# osc.net
KiCad netlist of a schematic drawn in EAGLE
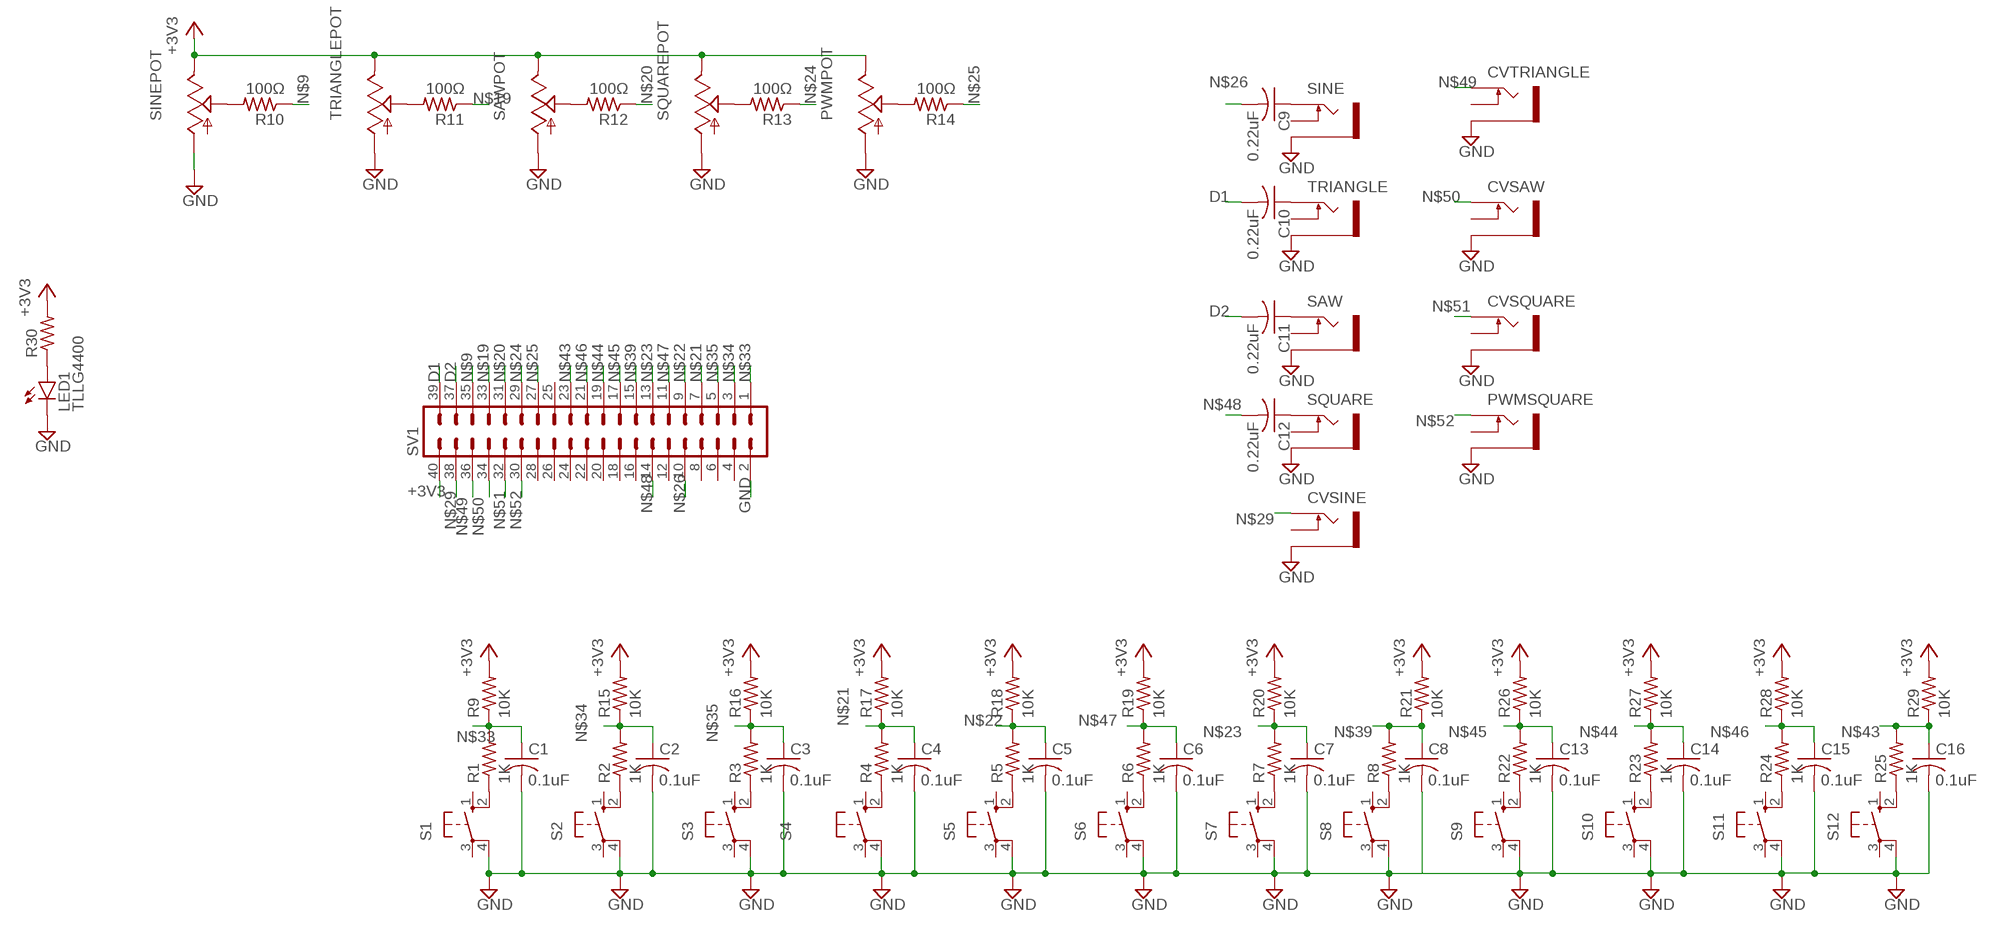
[diagram p0: schematic, sheet 1]

(export (version "E")
  (design (tool "Eeschema 10.0.6"))
  (components
    (comp (ref "C1")
      (value "0.1uF")
      (footprint "eagle-import:C025-024X044")
      (libsource (lib "eagle-import") (part "C-US025-024X044"))
    )
    (comp (ref "C2")
      (value "0.1uF")
      (footprint "eagle-import:C025-024X044")
      (libsource (lib "eagle-import") (part "C-US025-024X044"))
    )
    (comp (ref "C3")
      (value "0.1uF")
      (footprint "eagle-import:C025-024X044")
      (libsource (lib "eagle-import") (part "C-US025-024X044"))
    )
    (comp (ref "C4")
      (value "0.1uF")
      (footprint "eagle-import:C025-024X044")
      (libsource (lib "eagle-import") (part "C-US025-024X044"))
    )
    (comp (ref "C5")
      (value "0.1uF")
      (footprint "eagle-import:C025-024X044")
      (libsource (lib "eagle-import") (part "C-US025-024X044"))
    )
    (comp (ref "C6")
      (value "0.1uF")
      (footprint "eagle-import:C025-024X044")
      (libsource (lib "eagle-import") (part "C-US025-024X044"))
    )
    (comp (ref "C7")
      (value "0.1uF")
      (footprint "eagle-import:C025-024X044")
      (libsource (lib "eagle-import") (part "C-US025-024X044"))
    )
    (comp (ref "C8")
      (value "0.1uF")
      (footprint "eagle-import:C025-024X044")
      (libsource (lib "eagle-import") (part "C-US025-024X044"))
    )
    (comp (ref "C9")
      (value "0.22uF")
      (footprint "eagle-import:C025-024X044")
      (libsource (lib "eagle-import") (part "C-US025-024X044"))
    )
    (comp (ref "C10")
      (value "0.22uF")
      (footprint "eagle-import:C025-024X044")
      (libsource (lib "eagle-import") (part "C-US025-024X044"))
    )
    (comp (ref "C11")
      (value "0.22uF")
      (footprint "eagle-import:C025-024X044")
      (libsource (lib "eagle-import") (part "C-US025-024X044"))
    )
    (comp (ref "C12")
      (value "0.22uF")
      (footprint "eagle-import:C025-024X044")
      (libsource (lib "eagle-import") (part "C-US025-024X044"))
    )
    (comp (ref "C13")
      (value "0.1uF")
      (footprint "eagle-import:C025-024X044")
      (libsource (lib "eagle-import") (part "C-US025-024X044"))
    )
    (comp (ref "C14")
      (value "0.1uF")
      (footprint "eagle-import:C025-024X044")
      (libsource (lib "eagle-import") (part "C-US025-024X044"))
    )
    (comp (ref "C15")
      (value "0.1uF")
      (footprint "eagle-import:C025-024X044")
      (libsource (lib "eagle-import") (part "C-US025-024X044"))
    )
    (comp (ref "C16")
      (value "0.1uF")
      (footprint "eagle-import:C025-024X044")
      (libsource (lib "eagle-import") (part "C-US025-024X044"))
    )
    (comp (ref "CVSAW")
      (value "THONKICONNNEW")
      (footprint "eagle-import:WQP-PJ301M-12_JACK")
      (libsource (lib "eagle-import") (part "THONKICONNNEW"))
    )
    (comp (ref "CVSINE")
      (value "THONKICONNNEW")
      (footprint "eagle-import:WQP-PJ301M-12_JACK")
      (libsource (lib "eagle-import") (part "THONKICONNNEW"))
    )
    (comp (ref "CVSQUARE")
      (value "THONKICONNNEW")
      (footprint "eagle-import:WQP-PJ301M-12_JACK")
      (libsource (lib "eagle-import") (part "THONKICONNNEW"))
    )
    (comp (ref "CVTRIANGLE")
      (value "THONKICONNNEW")
      (footprint "eagle-import:WQP-PJ301M-12_JACK")
      (libsource (lib "eagle-import") (part "THONKICONNNEW"))
    )
    (comp (ref "LED1")
      (value "TLLG4400")
      (footprint "eagle-import:LED3MM")
      (fields (field (name "MF") "VISHAY SEMICONDUCTOR"))
      (libsource (lib "eagle-import") (part "TLLG4400"))
    )
    (comp (ref "PWMPOT")
      (value "9MM_SNAP-IN_POT_")
      (footprint "eagle-import:9MM_SNAP-IN_POT")
      (libsource (lib "eagle-import") (part "9MM_SNAP-IN_POT_"))
    )
    (comp (ref "PWMSQUARE")
      (value "THONKICONNNEW")
      (footprint "eagle-import:WQP-PJ301M-12_JACK")
      (libsource (lib "eagle-import") (part "THONKICONNNEW"))
    )
    (comp (ref "R1")
      (value "1K")
      (footprint "eagle-import:0207_10")
      (libsource (lib "eagle-import") (part "R-US_0207/10"))
    )
    (comp (ref "R2")
      (value "1K")
      (footprint "eagle-import:0207_10")
      (libsource (lib "eagle-import") (part "R-US_0207/10"))
    )
    (comp (ref "R3")
      (value "1K")
      (footprint "eagle-import:0207_10")
      (libsource (lib "eagle-import") (part "R-US_0207/10"))
    )
    (comp (ref "R4")
      (value "1K")
      (footprint "eagle-import:0207_10")
      (libsource (lib "eagle-import") (part "R-US_0207/10"))
    )
    (comp (ref "R5")
      (value "1K")
      (footprint "eagle-import:0207_10")
      (libsource (lib "eagle-import") (part "R-US_0207/10"))
    )
    (comp (ref "R6")
      (value "1K")
      (footprint "eagle-import:0207_10")
      (libsource (lib "eagle-import") (part "R-US_0207/10"))
    )
    (comp (ref "R7")
      (value "1K")
      (footprint "eagle-import:0207_10")
      (libsource (lib "eagle-import") (part "R-US_0207/10"))
    )
    (comp (ref "R8")
      (value "1K")
      (footprint "eagle-import:0207_10")
      (libsource (lib "eagle-import") (part "R-US_0207/10"))
    )
    (comp (ref "R9")
      (value "10K")
      (footprint "eagle-import:0207_10")
      (libsource (lib "eagle-import") (part "R-US_0207/10"))
    )
    (comp (ref "R10")
      (value "100Ω")
      (footprint "eagle-import:0207_10")
      (libsource (lib "eagle-import") (part "R-US_0207/10"))
    )
    (comp (ref "R11")
      (value "100Ω")
      (footprint "eagle-import:0207_10")
      (libsource (lib "eagle-import") (part "R-US_0207/10"))
    )
    (comp (ref "R12")
      (value "100Ω")
      (footprint "eagle-import:0207_10")
      (libsource (lib "eagle-import") (part "R-US_0207/10"))
    )
    (comp (ref "R13")
      (value "100Ω")
      (footprint "eagle-import:0207_10")
      (libsource (lib "eagle-import") (part "R-US_0207/10"))
    )
    (comp (ref "R14")
      (value "100Ω")
      (footprint "eagle-import:0207_10")
      (libsource (lib "eagle-import") (part "R-US_0207/10"))
    )
    (comp (ref "R15")
      (value "10K")
      (footprint "eagle-import:0207_10")
      (libsource (lib "eagle-import") (part "R-US_0207/10"))
    )
    (comp (ref "R16")
      (value "10K")
      (footprint "eagle-import:0207_10")
      (libsource (lib "eagle-import") (part "R-US_0207/10"))
    )
    (comp (ref "R17")
      (value "10K")
      (footprint "eagle-import:0207_10")
      (libsource (lib "eagle-import") (part "R-US_0207/10"))
    )
    (comp (ref "R18")
      (value "10K")
      (footprint "eagle-import:0207_10")
      (libsource (lib "eagle-import") (part "R-US_0207/10"))
    )
    (comp (ref "R19")
      (value "10K")
      (footprint "eagle-import:0207_10")
      (libsource (lib "eagle-import") (part "R-US_0207/10"))
    )
    (comp (ref "R20")
      (value "10K")
      (footprint "eagle-import:0207_10")
      (libsource (lib "eagle-import") (part "R-US_0207/10"))
    )
    (comp (ref "R21")
      (value "10K")
      (footprint "eagle-import:0207_10")
      (libsource (lib "eagle-import") (part "R-US_0207/10"))
    )
    (comp (ref "R22")
      (value "1K")
      (footprint "eagle-import:0207_10")
      (libsource (lib "eagle-import") (part "R-US_0207/10"))
    )
    (comp (ref "R23")
      (value "1K")
      (footprint "eagle-import:0207_10")
      (libsource (lib "eagle-import") (part "R-US_0207/10"))
    )
    (comp (ref "R24")
      (value "1K")
      (footprint "eagle-import:0207_10")
      (libsource (lib "eagle-import") (part "R-US_0207/10"))
    )
    (comp (ref "R25")
      (value "1K")
      (footprint "eagle-import:0207_10")
      (libsource (lib "eagle-import") (part "R-US_0207/10"))
    )
    (comp (ref "R26")
      (value "10K")
      (footprint "eagle-import:0207_10")
      (libsource (lib "eagle-import") (part "R-US_0207/10"))
    )
    (comp (ref "R27")
      (value "10K")
      (footprint "eagle-import:0207_10")
      (libsource (lib "eagle-import") (part "R-US_0207/10"))
    )
    (comp (ref "R28")
      (value "10K")
      (footprint "eagle-import:0207_10")
      (libsource (lib "eagle-import") (part "R-US_0207/10"))
    )
    (comp (ref "R29")
      (value "10K")
      (footprint "eagle-import:0207_10")
      (libsource (lib "eagle-import") (part "R-US_0207/10"))
    )
    (comp (ref "R30")
      (value "R-US_0207/10")
      (footprint "eagle-import:0207_10")
      (libsource (lib "eagle-import") (part "R-US_0207/10"))
    )
    (comp (ref "S1")
      (value "10-XX")
      (footprint "eagle-import:B3F-10XX")
      (fields (field (name "MPN") "B3F-1000"))
      (libsource (lib "eagle-import") (part "10-XX"))
    )
    (comp (ref "S2")
      (value "10-XX")
      (footprint "eagle-import:B3F-10XX")
      (fields (field (name "MPN") "B3F-1000"))
      (libsource (lib "eagle-import") (part "10-XX"))
    )
    (comp (ref "S3")
      (value "10-XX")
      (footprint "eagle-import:B3F-10XX")
      (fields (field (name "MPN") "B3F-1000"))
      (libsource (lib "eagle-import") (part "10-XX"))
    )
    (comp (ref "S4")
      (value "10-XX")
      (footprint "eagle-import:B3F-10XX")
      (fields (field (name "MPN") "B3F-1000"))
      (libsource (lib "eagle-import") (part "10-XX"))
    )
    (comp (ref "S5")
      (value "10-XX")
      (footprint "eagle-import:B3F-10XX")
      (fields (field (name "MPN") "B3F-1000"))
      (libsource (lib "eagle-import") (part "10-XX"))
    )
    (comp (ref "S6")
      (value "10-XX")
      (footprint "eagle-import:B3F-10XX")
      (fields (field (name "MPN") "B3F-1000"))
      (libsource (lib "eagle-import") (part "10-XX"))
    )
    (comp (ref "S7")
      (value "10-XX")
      (footprint "eagle-import:B3F-10XX")
      (fields (field (name "MPN") "B3F-1000"))
      (libsource (lib "eagle-import") (part "10-XX"))
    )
    (comp (ref "S8")
      (value "10-XX")
      (footprint "eagle-import:B3F-10XX")
      (fields (field (name "MPN") "B3F-1000"))
      (libsource (lib "eagle-import") (part "10-XX"))
    )
    (comp (ref "S9")
      (value "10-XX")
      (footprint "eagle-import:B3F-10XX")
      (fields (field (name "MPN") "B3F-1000"))
      (libsource (lib "eagle-import") (part "10-XX"))
    )
    (comp (ref "S10")
      (value "10-XX")
      (footprint "eagle-import:B3F-10XX")
      (fields (field (name "MPN") "B3F-1000"))
      (libsource (lib "eagle-import") (part "10-XX"))
    )
    (comp (ref "S11")
      (value "10-XX")
      (footprint "eagle-import:B3F-10XX")
      (fields (field (name "MPN") "B3F-1000"))
      (libsource (lib "eagle-import") (part "10-XX"))
    )
    (comp (ref "S12")
      (value "10-XX")
      (footprint "eagle-import:B3F-10XX")
      (fields (field (name "MPN") "B3F-1000"))
      (libsource (lib "eagle-import") (part "10-XX"))
    )
    (comp (ref "SAW")
      (value "THONKICONNNEW")
      (footprint "eagle-import:WQP-PJ301M-12_JACK")
      (libsource (lib "eagle-import") (part "THONKICONNNEW"))
    )
    (comp (ref "SAWPOT")
      (value "9MM_SNAP-IN_POT_")
      (footprint "eagle-import:9MM_SNAP-IN_POT")
      (libsource (lib "eagle-import") (part "9MM_SNAP-IN_POT_"))
    )
    (comp (ref "SINE")
      (value "THONKICONNNEW")
      (footprint "eagle-import:WQP-PJ301M-12_JACK")
      (libsource (lib "eagle-import") (part "THONKICONNNEW"))
    )
    (comp (ref "SINEPOT")
      (value "9MM_SNAP-IN_POT_")
      (footprint "eagle-import:9MM_SNAP-IN_POT")
      (libsource (lib "eagle-import") (part "9MM_SNAP-IN_POT_"))
    )
    (comp (ref "SQUARE")
      (value "THONKICONNNEW")
      (footprint "eagle-import:WQP-PJ301M-12_JACK")
      (libsource (lib "eagle-import") (part "THONKICONNNEW"))
    )
    (comp (ref "SQUAREPOT")
      (value "9MM_SNAP-IN_POT_")
      (footprint "eagle-import:9MM_SNAP-IN_POT")
      (libsource (lib "eagle-import") (part "9MM_SNAP-IN_POT_"))
    )
    (comp (ref "SV1")
      (value "MA20-2")
      (footprint "eagle-import:MA20-2")
      (libsource (lib "eagle-import") (part "MA20-2"))
    )
    (comp (ref "TRIANGLE")
      (value "THONKICONNNEW")
      (footprint "eagle-import:WQP-PJ301M-12_JACK")
      (libsource (lib "eagle-import") (part "THONKICONNNEW"))
    )
    (comp (ref "TRIANGLEPOT")
      (value "9MM_SNAP-IN_POT_")
      (footprint "eagle-import:9MM_SNAP-IN_POT")
      (libsource (lib "eagle-import") (part "9MM_SNAP-IN_POT_"))
    )
  )
  (nets
    (net (code "1") (name "+3V3") (class "Default")
      (node (ref "PWMPOT") (pin "3") (pinfunction "E_3") (pintype "passive"))
      (node (ref "R15") (pin "2") (pinfunction "2_2") (pintype "passive"))
      (node (ref "R16") (pin "2") (pinfunction "2_2") (pintype "passive"))
      (node (ref "R17") (pin "2") (pinfunction "2_2") (pintype "passive"))
      (node (ref "R18") (pin "2") (pinfunction "2_2") (pintype "passive"))
      (node (ref "R19") (pin "2") (pinfunction "2_2") (pintype "passive"))
      (node (ref "R20") (pin "2") (pinfunction "2_2") (pintype "passive"))
      (node (ref "R21") (pin "2") (pinfunction "2_2") (pintype "passive"))
      (node (ref "R26") (pin "2") (pinfunction "2_2") (pintype "passive"))
      (node (ref "R27") (pin "2") (pinfunction "2_2") (pintype "passive"))
      (node (ref "R28") (pin "2") (pinfunction "2_2") (pintype "passive"))
      (node (ref "R29") (pin "2") (pinfunction "2_2") (pintype "passive"))
      (node (ref "R30") (pin "2") (pinfunction "2_2") (pintype "passive"))
      (node (ref "R9") (pin "2") (pinfunction "2_2") (pintype "passive"))
      (node (ref "SAWPOT") (pin "3") (pinfunction "E_3") (pintype "passive"))
      (node (ref "SINEPOT") (pin "3") (pinfunction "E_3") (pintype "passive"))
      (node (ref "SQUAREPOT") (pin "3") (pinfunction "E_3") (pintype "passive"))
      (node (ref "SV1") (pin "40") (pinfunction "40_40") (pintype "passive"))
      (node (ref "TRIANGLEPOT") (pin "3") (pinfunction "E_3") (pintype "passive"))
    )
    (net (code "2") (name "/D1") (class "Default")
      (node (ref "C10") (pin "2") (pinfunction "2_2") (pintype "passive"))
      (node (ref "SV1") (pin "39") (pinfunction "39_39") (pintype "passive"))
    )
    (net (code "3") (name "/D2") (class "Default")
      (node (ref "C11") (pin "2") (pinfunction "2_2") (pintype "passive"))
      (node (ref "SV1") (pin "37") (pinfunction "37_37") (pintype "passive"))
    )
    (net (code "4") (name "/N$9") (class "Default")
      (node (ref "R10") (pin "1") (pinfunction "1_1") (pintype "passive"))
      (node (ref "SV1") (pin "35") (pinfunction "35_35") (pintype "passive"))
    )
    (net (code "5") (name "/N$19") (class "Default")
      (node (ref "R11") (pin "1") (pinfunction "1_1") (pintype "passive"))
      (node (ref "SV1") (pin "33") (pinfunction "33_33") (pintype "passive"))
    )
    (net (code "6") (name "/N$20") (class "Default")
      (node (ref "R12") (pin "1") (pinfunction "1_1") (pintype "passive"))
      (node (ref "SV1") (pin "31") (pinfunction "31_31") (pintype "passive"))
    )
    (net (code "7") (name "/N$21") (class "Default")
      (node (ref "C4") (pin "1") (pinfunction "1_1") (pintype "passive"))
      (node (ref "R17") (pin "1") (pinfunction "1_1") (pintype "passive"))
      (node (ref "R4") (pin "2") (pinfunction "2_2") (pintype "passive"))
      (node (ref "SV1") (pin "7") (pinfunction "7_7") (pintype "passive"))
    )
    (net (code "8") (name "/N$22") (class "Default")
      (node (ref "C5") (pin "1") (pinfunction "1_1") (pintype "passive"))
      (node (ref "R18") (pin "1") (pinfunction "1_1") (pintype "passive"))
      (node (ref "R5") (pin "2") (pinfunction "2_2") (pintype "passive"))
      (node (ref "SV1") (pin "9") (pinfunction "9_9") (pintype "passive"))
    )
    (net (code "9") (name "/N$23") (class "Default")
      (node (ref "C7") (pin "1") (pinfunction "1_1") (pintype "passive"))
      (node (ref "R20") (pin "1") (pinfunction "1_1") (pintype "passive"))
      (node (ref "R7") (pin "2") (pinfunction "2_2") (pintype "passive"))
      (node (ref "SV1") (pin "13") (pinfunction "13_13") (pintype "passive"))
    )
    (net (code "10") (name "/N$24") (class "Default")
      (node (ref "R13") (pin "1") (pinfunction "1_1") (pintype "passive"))
      (node (ref "SV1") (pin "29") (pinfunction "29_29") (pintype "passive"))
    )
    (net (code "11") (name "/N$25") (class "Default")
      (node (ref "R14") (pin "1") (pinfunction "1_1") (pintype "passive"))
      (node (ref "SV1") (pin "27") (pinfunction "27_27") (pintype "passive"))
    )
    (net (code "12") (name "/N$26") (class "Default")
      (node (ref "C9") (pin "2") (pinfunction "2_2") (pintype "passive"))
      (node (ref "SV1") (pin "10") (pinfunction "10_10") (pintype "passive"))
    )
    (net (code "13") (name "/N$29") (class "Default")
      (node (ref "CVSINE") (pin "P$1_TIP") (pinfunction "TIP_P$1_TIP") (pintype "passive"))
      (node (ref "SV1") (pin "38") (pinfunction "38_38") (pintype "passive"))
    )
    (net (code "14") (name "/N$33") (class "Default")
      (node (ref "C1") (pin "1") (pinfunction "1_1") (pintype "passive"))
      (node (ref "R1") (pin "2") (pinfunction "2_2") (pintype "passive"))
      (node (ref "R9") (pin "1") (pinfunction "1_1") (pintype "passive"))
      (node (ref "SV1") (pin "1") (pinfunction "1_1") (pintype "passive"))
    )
    (net (code "15") (name "/N$34") (class "Default")
      (node (ref "C2") (pin "1") (pinfunction "1_1") (pintype "passive"))
      (node (ref "R15") (pin "1") (pinfunction "1_1") (pintype "passive"))
      (node (ref "R2") (pin "2") (pinfunction "2_2") (pintype "passive"))
      (node (ref "SV1") (pin "3") (pinfunction "3_3") (pintype "passive"))
    )
    (net (code "16") (name "/N$35") (class "Default")
      (node (ref "C3") (pin "1") (pinfunction "1_1") (pintype "passive"))
      (node (ref "R16") (pin "1") (pinfunction "1_1") (pintype "passive"))
      (node (ref "R3") (pin "2") (pinfunction "2_2") (pintype "passive"))
      (node (ref "SV1") (pin "5") (pinfunction "5_5") (pintype "passive"))
    )
    (net (code "17") (name "/N$39") (class "Default")
      (node (ref "C8") (pin "1") (pinfunction "1_1") (pintype "passive"))
      (node (ref "R21") (pin "1") (pinfunction "1_1") (pintype "passive"))
      (node (ref "R8") (pin "2") (pinfunction "2_2") (pintype "passive"))
      (node (ref "SV1") (pin "15") (pinfunction "15_15") (pintype "passive"))
    )
    (net (code "18") (name "/N$43") (class "Default")
      (node (ref "C16") (pin "1") (pinfunction "1_1") (pintype "passive"))
      (node (ref "R25") (pin "2") (pinfunction "2_2") (pintype "passive"))
      (node (ref "R29") (pin "1") (pinfunction "1_1") (pintype "passive"))
      (node (ref "SV1") (pin "23") (pinfunction "23_23") (pintype "passive"))
    )
    (net (code "19") (name "/N$44") (class "Default")
      (node (ref "C14") (pin "1") (pinfunction "1_1") (pintype "passive"))
      (node (ref "R23") (pin "2") (pinfunction "2_2") (pintype "passive"))
      (node (ref "R27") (pin "1") (pinfunction "1_1") (pintype "passive"))
      (node (ref "SV1") (pin "19") (pinfunction "19_19") (pintype "passive"))
    )
    (net (code "20") (name "/N$45") (class "Default")
      (node (ref "C13") (pin "1") (pinfunction "1_1") (pintype "passive"))
      (node (ref "R22") (pin "2") (pinfunction "2_2") (pintype "passive"))
      (node (ref "R26") (pin "1") (pinfunction "1_1") (pintype "passive"))
      (node (ref "SV1") (pin "17") (pinfunction "17_17") (pintype "passive"))
    )
    (net (code "21") (name "/N$46") (class "Default")
      (node (ref "C15") (pin "1") (pinfunction "1_1") (pintype "passive"))
      (node (ref "R24") (pin "2") (pinfunction "2_2") (pintype "passive"))
      (node (ref "R28") (pin "1") (pinfunction "1_1") (pintype "passive"))
      (node (ref "SV1") (pin "21") (pinfunction "21_21") (pintype "passive"))
    )
    (net (code "22") (name "/N$47") (class "Default")
      (node (ref "C6") (pin "1") (pinfunction "1_1") (pintype "passive"))
      (node (ref "R19") (pin "1") (pinfunction "1_1") (pintype "passive"))
      (node (ref "R6") (pin "2") (pinfunction "2_2") (pintype "passive"))
      (node (ref "SV1") (pin "11") (pinfunction "11_11") (pintype "passive"))
    )
    (net (code "23") (name "/N$48") (class "Default")
      (node (ref "C12") (pin "2") (pinfunction "2_2") (pintype "passive"))
      (node (ref "SV1") (pin "14") (pinfunction "14_14") (pintype "passive"))
    )
    (net (code "24") (name "/N$49") (class "Default")
      (node (ref "CVTRIANGLE") (pin "P$1_TIP") (pinfunction "TIP_P$1_TIP") (pintype "passive"))
      (node (ref "SV1") (pin "36") (pinfunction "36_36") (pintype "passive"))
    )
    (net (code "25") (name "/N$50") (class "Default")
      (node (ref "CVSAW") (pin "P$1_TIP") (pinfunction "TIP_P$1_TIP") (pintype "passive"))
      (node (ref "SV1") (pin "34") (pinfunction "34_34") (pintype "passive"))
    )
    (net (code "26") (name "/N$51") (class "Default")
      (node (ref "CVSQUARE") (pin "P$1_TIP") (pinfunction "TIP_P$1_TIP") (pintype "passive"))
      (node (ref "SV1") (pin "32") (pinfunction "32_32") (pintype "passive"))
    )
    (net (code "27") (name "/N$52") (class "Default")
      (node (ref "PWMSQUARE") (pin "P$1_TIP") (pinfunction "TIP_P$1_TIP") (pintype "passive"))
      (node (ref "SV1") (pin "30") (pinfunction "30_30") (pintype "passive"))
    )
    (net (code "28") (name "GND") (class "Default")
      (node (ref "C1") (pin "2") (pinfunction "2_2") (pintype "passive"))
      (node (ref "C13") (pin "2") (pinfunction "2_2") (pintype "passive"))
      (node (ref "C14") (pin "2") (pinfunction "2_2") (pintype "passive"))
      (node (ref "C15") (pin "2") (pinfunction "2_2") (pintype "passive"))
      (node (ref "C16") (pin "2") (pinfunction "2_2") (pintype "passive"))
      (node (ref "C2") (pin "2") (pinfunction "2_2") (pintype "passive"))
      (node (ref "C3") (pin "2") (pinfunction "2_2") (pintype "passive"))
      (node (ref "C4") (pin "2") (pinfunction "2_2") (pintype "passive"))
      (node (ref "C5") (pin "2") (pinfunction "2_2") (pintype "passive"))
      (node (ref "C6") (pin "2") (pinfunction "2_2") (pintype "passive"))
      (node (ref "C7") (pin "2") (pinfunction "2_2") (pintype "passive"))
      (node (ref "C8") (pin "2") (pinfunction "2_2") (pintype "passive"))
      (node (ref "CVSAW") (pin "P$3_SLEEVE") (pinfunction "SLEEVE_P$3_SLEEVE") (pintype "passive"))
      (node (ref "CVSINE") (pin "P$3_SLEEVE") (pinfunction "SLEEVE_P$3_SLEEVE") (pintype "passive"))
      (node (ref "CVSQUARE") (pin "P$3_SLEEVE") (pinfunction "SLEEVE_P$3_SLEEVE") (pintype "passive"))
      (node (ref "CVTRIANGLE") (pin "P$3_SLEEVE") (pinfunction "SLEEVE_P$3_SLEEVE") (pintype "passive"))
      (node (ref "LED1") (pin "K") (pinfunction "C_K") (pintype "passive"))
      (node (ref "PWMPOT") (pin "1") (pinfunction "A_1") (pintype "passive"))
      (node (ref "PWMSQUARE") (pin "P$3_SLEEVE") (pinfunction "SLEEVE_P$3_SLEEVE") (pintype "passive"))
      (node (ref "S1") (pin "4") (pinfunction "P1_4") (pintype "passive"))
      (node (ref "S10") (pin "4") (pinfunction "P1_4") (pintype "passive"))
      (node (ref "S11") (pin "4") (pinfunction "P1_4") (pintype "passive"))
      (node (ref "S12") (pin "4") (pinfunction "P1_4") (pintype "passive"))
      (node (ref "S2") (pin "4") (pinfunction "P1_4") (pintype "passive"))
      (node (ref "S3") (pin "4") (pinfunction "P1_4") (pintype "passive"))
      (node (ref "S4") (pin "4") (pinfunction "P1_4") (pintype "passive"))
      (node (ref "S5") (pin "4") (pinfunction "P1_4") (pintype "passive"))
      (node (ref "S6") (pin "4") (pinfunction "P1_4") (pintype "passive"))
      (node (ref "S7") (pin "4") (pinfunction "P1_4") (pintype "passive"))
      (node (ref "S8") (pin "4") (pinfunction "P1_4") (pintype "passive"))
      (node (ref "S9") (pin "4") (pinfunction "P1_4") (pintype "passive"))
      (node (ref "SAW") (pin "P$3_SLEEVE") (pinfunction "SLEEVE_P$3_SLEEVE") (pintype "passive"))
      (node (ref "SAWPOT") (pin "1") (pinfunction "A_1") (pintype "passive"))
      (node (ref "SINE") (pin "P$3_SLEEVE") (pinfunction "SLEEVE_P$3_SLEEVE") (pintype "passive"))
      (node (ref "SINEPOT") (pin "1") (pinfunction "A_1") (pintype "passive"))
      (node (ref "SQUARE") (pin "P$3_SLEEVE") (pinfunction "SLEEVE_P$3_SLEEVE") (pintype "passive"))
      (node (ref "SQUAREPOT") (pin "1") (pinfunction "A_1") (pintype "passive"))
      (node (ref "SV1") (pin "2") (pinfunction "2_2") (pintype "passive"))
      (node (ref "TRIANGLE") (pin "P$3_SLEEVE") (pinfunction "SLEEVE_P$3_SLEEVE") (pintype "passive"))
      (node (ref "TRIANGLEPOT") (pin "1") (pinfunction "A_1") (pintype "passive"))
    )
    (net (code "29") (name "Net-(LED1-PadA)") (class "Default")
      (node (ref "LED1") (pin "A") (pinfunction "A_A") (pintype "passive"))
      (node (ref "R30") (pin "1") (pinfunction "1_1") (pintype "passive"))
    )
    (net (code "30") (name "Net-(PWMPOT-S)") (class "Default")
      (node (ref "PWMPOT") (pin "2") (pinfunction "S_2") (pintype "passive"))
      (node (ref "R14") (pin "2") (pinfunction "2_2") (pintype "passive"))
    )
    (net (code "31") (name "Net-(S1-S1)") (class "Default")
      (node (ref "R1") (pin "1") (pinfunction "1_1") (pintype "passive"))
      (node (ref "S1") (pin "2") (pinfunction "S1_2") (pintype "passive"))
    )
    (net (code "32") (name "Net-(S2-S1)") (class "Default")
      (node (ref "R2") (pin "1") (pinfunction "1_1") (pintype "passive"))
      (node (ref "S2") (pin "2") (pinfunction "S1_2") (pintype "passive"))
    )
    (net (code "33") (name "Net-(S3-S1)") (class "Default")
      (node (ref "R3") (pin "1") (pinfunction "1_1") (pintype "passive"))
      (node (ref "S3") (pin "2") (pinfunction "S1_2") (pintype "passive"))
    )
    (net (code "34") (name "Net-(S4-S1)") (class "Default")
      (node (ref "R4") (pin "1") (pinfunction "1_1") (pintype "passive"))
      (node (ref "S4") (pin "2") (pinfunction "S1_2") (pintype "passive"))
    )
    (net (code "35") (name "Net-(S5-S1)") (class "Default")
      (node (ref "R5") (pin "1") (pinfunction "1_1") (pintype "passive"))
      (node (ref "S5") (pin "2") (pinfunction "S1_2") (pintype "passive"))
    )
    (net (code "36") (name "Net-(S6-S1)") (class "Default")
      (node (ref "R6") (pin "1") (pinfunction "1_1") (pintype "passive"))
      (node (ref "S6") (pin "2") (pinfunction "S1_2") (pintype "passive"))
    )
    (net (code "37") (name "Net-(S7-S1)") (class "Default")
      (node (ref "R7") (pin "1") (pinfunction "1_1") (pintype "passive"))
      (node (ref "S7") (pin "2") (pinfunction "S1_2") (pintype "passive"))
    )
    (net (code "38") (name "Net-(S8-S1)") (class "Default")
      (node (ref "R8") (pin "1") (pinfunction "1_1") (pintype "passive"))
      (node (ref "S8") (pin "2") (pinfunction "S1_2") (pintype "passive"))
    )
    (net (code "39") (name "Net-(S9-S1)") (class "Default")
      (node (ref "R22") (pin "1") (pinfunction "1_1") (pintype "passive"))
      (node (ref "S9") (pin "2") (pinfunction "S1_2") (pintype "passive"))
    )
    (net (code "40") (name "Net-(S10-S1)") (class "Default")
      (node (ref "R23") (pin "1") (pinfunction "1_1") (pintype "passive"))
      (node (ref "S10") (pin "2") (pinfunction "S1_2") (pintype "passive"))
    )
    (net (code "41") (name "Net-(S11-S1)") (class "Default")
      (node (ref "R24") (pin "1") (pinfunction "1_1") (pintype "passive"))
      (node (ref "S11") (pin "2") (pinfunction "S1_2") (pintype "passive"))
    )
    (net (code "42") (name "Net-(S12-S1)") (class "Default")
      (node (ref "R25") (pin "1") (pinfunction "1_1") (pintype "passive"))
      (node (ref "S12") (pin "2") (pinfunction "S1_2") (pintype "passive"))
    )
    (net (code "43") (name "Net-(SAW-TIP)") (class "Default")
      (node (ref "C11") (pin "1") (pinfunction "1_1") (pintype "passive"))
      (node (ref "SAW") (pin "P$1_TIP") (pinfunction "TIP_P$1_TIP") (pintype "passive"))
    )
    (net (code "44") (name "Net-(SAWPOT-S)") (class "Default")
      (node (ref "R12") (pin "2") (pinfunction "2_2") (pintype "passive"))
      (node (ref "SAWPOT") (pin "2") (pinfunction "S_2") (pintype "passive"))
    )
    (net (code "45") (name "Net-(SINE-TIP)") (class "Default")
      (node (ref "C9") (pin "1") (pinfunction "1_1") (pintype "passive"))
      (node (ref "SINE") (pin "P$1_TIP") (pinfunction "TIP_P$1_TIP") (pintype "passive"))
    )
    (net (code "46") (name "Net-(SINEPOT-S)") (class "Default")
      (node (ref "R10") (pin "2") (pinfunction "2_2") (pintype "passive"))
      (node (ref "SINEPOT") (pin "2") (pinfunction "S_2") (pintype "passive"))
    )
    (net (code "47") (name "Net-(SQUARE-TIP)") (class "Default")
      (node (ref "C12") (pin "1") (pinfunction "1_1") (pintype "passive"))
      (node (ref "SQUARE") (pin "P$1_TIP") (pinfunction "TIP_P$1_TIP") (pintype "passive"))
    )
    (net (code "48") (name "Net-(SQUAREPOT-S)") (class "Default")
      (node (ref "R13") (pin "2") (pinfunction "2_2") (pintype "passive"))
      (node (ref "SQUAREPOT") (pin "2") (pinfunction "S_2") (pintype "passive"))
    )
    (net (code "49") (name "Net-(TRIANGLE-TIP)") (class "Default")
      (node (ref "C10") (pin "1") (pinfunction "1_1") (pintype "passive"))
      (node (ref "TRIANGLE") (pin "P$1_TIP") (pinfunction "TIP_P$1_TIP") (pintype "passive"))
    )
    (net (code "50") (name "Net-(TRIANGLEPOT-S)") (class "Default")
      (node (ref "R11") (pin "2") (pinfunction "2_2") (pintype "passive"))
      (node (ref "TRIANGLEPOT") (pin "2") (pinfunction "S_2") (pintype "passive"))
    )
    (net (code "51") (name "unconnected-(CVSAW-SWITCH-PadP$2_SWITCH)") (class "Default")
      (node (ref "CVSAW") (pin "P$2_SWITCH") (pinfunction "SWITCH_P$2_SWITCH") (pintype "passive"))
    )
    (net (code "52") (name "unconnected-(CVSINE-SWITCH-PadP$2_SWITCH)") (class "Default")
      (node (ref "CVSINE") (pin "P$2_SWITCH") (pinfunction "SWITCH_P$2_SWITCH") (pintype "passive"))
    )
    (net (code "53") (name "unconnected-(CVSQUARE-SWITCH-PadP$2_SWITCH)") (class "Default")
      (node (ref "CVSQUARE") (pin "P$2_SWITCH") (pinfunction "SWITCH_P$2_SWITCH") (pintype "passive"))
    )
    (net (code "54") (name "unconnected-(CVTRIANGLE-SWITCH-PadP$2_SWITCH)") (class "Default")
      (node (ref "CVTRIANGLE") (pin "P$2_SWITCH") (pinfunction "SWITCH_P$2_SWITCH") (pintype "passive"))
    )
    (net (code "55") (name "unconnected-(PWMSQUARE-SWITCH-PadP$2_SWITCH)") (class "Default")
      (node (ref "PWMSQUARE") (pin "P$2_SWITCH") (pinfunction "SWITCH_P$2_SWITCH") (pintype "passive"))
    )
    (net (code "56") (name "unconnected-(S1-P-Pad3)") (class "Default")
      (node (ref "S1") (pin "3") (pinfunction "P_3") (pintype "passive"))
    )
    (net (code "57") (name "unconnected-(S1-S-Pad1)") (class "Default")
      (node (ref "S1") (pin "1") (pinfunction "S_1") (pintype "passive"))
    )
    (net (code "58") (name "unconnected-(S2-P-Pad3)") (class "Default")
      (node (ref "S2") (pin "3") (pinfunction "P_3") (pintype "passive"))
    )
    (net (code "59") (name "unconnected-(S2-S-Pad1)") (class "Default")
      (node (ref "S2") (pin "1") (pinfunction "S_1") (pintype "passive"))
    )
    (net (code "60") (name "unconnected-(S3-P-Pad3)") (class "Default")
      (node (ref "S3") (pin "3") (pinfunction "P_3") (pintype "passive"))
    )
    (net (code "61") (name "unconnected-(S3-S-Pad1)") (class "Default")
      (node (ref "S3") (pin "1") (pinfunction "S_1") (pintype "passive"))
    )
    (net (code "62") (name "unconnected-(S4-P-Pad3)") (class "Default")
      (node (ref "S4") (pin "3") (pinfunction "P_3") (pintype "passive"))
    )
    (net (code "63") (name "unconnected-(S4-S-Pad1)") (class "Default")
      (node (ref "S4") (pin "1") (pinfunction "S_1") (pintype "passive"))
    )
    (net (code "64") (name "unconnected-(S5-P-Pad3)") (class "Default")
      (node (ref "S5") (pin "3") (pinfunction "P_3") (pintype "passive"))
    )
    (net (code "65") (name "unconnected-(S5-S-Pad1)") (class "Default")
      (node (ref "S5") (pin "1") (pinfunction "S_1") (pintype "passive"))
    )
    (net (code "66") (name "unconnected-(S6-P-Pad3)") (class "Default")
      (node (ref "S6") (pin "3") (pinfunction "P_3") (pintype "passive"))
    )
    (net (code "67") (name "unconnected-(S6-S-Pad1)") (class "Default")
      (node (ref "S6") (pin "1") (pinfunction "S_1") (pintype "passive"))
    )
    (net (code "68") (name "unconnected-(S7-P-Pad3)") (class "Default")
      (node (ref "S7") (pin "3") (pinfunction "P_3") (pintype "passive"))
    )
    (net (code "69") (name "unconnected-(S7-S-Pad1)") (class "Default")
      (node (ref "S7") (pin "1") (pinfunction "S_1") (pintype "passive"))
    )
    (net (code "70") (name "unconnected-(S8-P-Pad3)") (class "Default")
      (node (ref "S8") (pin "3") (pinfunction "P_3") (pintype "passive"))
    )
    (net (code "71") (name "unconnected-(S8-S-Pad1)") (class "Default")
      (node (ref "S8") (pin "1") (pinfunction "S_1") (pintype "passive"))
    )
    (net (code "72") (name "unconnected-(S9-P-Pad3)") (class "Default")
      (node (ref "S9") (pin "3") (pinfunction "P_3") (pintype "passive"))
    )
    (net (code "73") (name "unconnected-(S9-S-Pad1)") (class "Default")
      (node (ref "S9") (pin "1") (pinfunction "S_1") (pintype "passive"))
    )
    (net (code "74") (name "unconnected-(S10-P-Pad3)") (class "Default")
      (node (ref "S10") (pin "3") (pinfunction "P_3") (pintype "passive"))
    )
    (net (code "75") (name "unconnected-(S10-S-Pad1)") (class "Default")
      (node (ref "S10") (pin "1") (pinfunction "S_1") (pintype "passive"))
    )
    (net (code "76") (name "unconnected-(S11-P-Pad3)") (class "Default")
      (node (ref "S11") (pin "3") (pinfunction "P_3") (pintype "passive"))
    )
    (net (code "77") (name "unconnected-(S11-S-Pad1)") (class "Default")
      (node (ref "S11") (pin "1") (pinfunction "S_1") (pintype "passive"))
    )
    (net (code "78") (name "unconnected-(S12-P-Pad3)") (class "Default")
      (node (ref "S12") (pin "3") (pinfunction "P_3") (pintype "passive"))
    )
    (net (code "79") (name "unconnected-(S12-S-Pad1)") (class "Default")
      (node (ref "S12") (pin "1") (pinfunction "S_1") (pintype "passive"))
    )
    (net (code "80") (name "unconnected-(SAW-SWITCH-PadP$2_SWITCH)") (class "Default")
      (node (ref "SAW") (pin "P$2_SWITCH") (pinfunction "SWITCH_P$2_SWITCH") (pintype "passive"))
    )
    (net (code "81") (name "unconnected-(SINE-SWITCH-PadP$2_SWITCH)") (class "Default")
      (node (ref "SINE") (pin "P$2_SWITCH") (pinfunction "SWITCH_P$2_SWITCH") (pintype "passive"))
    )
    (net (code "82") (name "unconnected-(SQUARE-SWITCH-PadP$2_SWITCH)") (class "Default")
      (node (ref "SQUARE") (pin "P$2_SWITCH") (pinfunction "SWITCH_P$2_SWITCH") (pintype "passive"))
    )
    (net (code "83") (name "unconnected-(SV1-Pad4)") (class "Default")
      (node (ref "SV1") (pin "4") (pinfunction "4_4") (pintype "passive"))
    )
    (net (code "84") (name "unconnected-(SV1-Pad6)") (class "Default")
      (node (ref "SV1") (pin "6") (pinfunction "6_6") (pintype "passive"))
    )
    (net (code "85") (name "unconnected-(SV1-Pad8)") (class "Default")
      (node (ref "SV1") (pin "8") (pinfunction "8_8") (pintype "passive"))
    )
    (net (code "86") (name "unconnected-(SV1-Pad12)") (class "Default")
      (node (ref "SV1") (pin "12") (pinfunction "12_12") (pintype "passive"))
    )
    (net (code "87") (name "unconnected-(SV1-Pad16)") (class "Default")
      (node (ref "SV1") (pin "16") (pinfunction "16_16") (pintype "passive"))
    )
    (net (code "88") (name "unconnected-(SV1-Pad18)") (class "Default")
      (node (ref "SV1") (pin "18") (pinfunction "18_18") (pintype "passive"))
    )
    (net (code "89") (name "unconnected-(SV1-Pad20)") (class "Default")
      (node (ref "SV1") (pin "20") (pinfunction "20_20") (pintype "passive"))
    )
    (net (code "90") (name "unconnected-(SV1-Pad22)") (class "Default")
      (node (ref "SV1") (pin "22") (pinfunction "22_22") (pintype "passive"))
    )
    (net (code "91") (name "unconnected-(SV1-Pad24)") (class "Default")
      (node (ref "SV1") (pin "24") (pinfunction "24_24") (pintype "passive"))
    )
    (net (code "92") (name "unconnected-(SV1-Pad25)") (class "Default")
      (node (ref "SV1") (pin "25") (pinfunction "25_25") (pintype "passive"))
    )
    (net (code "93") (name "unconnected-(SV1-Pad26)") (class "Default")
      (node (ref "SV1") (pin "26") (pinfunction "26_26") (pintype "passive"))
    )
    (net (code "94") (name "unconnected-(SV1-Pad28)") (class "Default")
      (node (ref "SV1") (pin "28") (pinfunction "28_28") (pintype "passive"))
    )
    (net (code "95") (name "unconnected-(TRIANGLE-SWITCH-PadP$2_SWITCH)") (class "Default")
      (node (ref "TRIANGLE") (pin "P$2_SWITCH") (pinfunction "SWITCH_P$2_SWITCH") (pintype "passive"))
    )
  )
)
